# MCU.net
KiCad netlist of a schematic drawn in Altium Designer
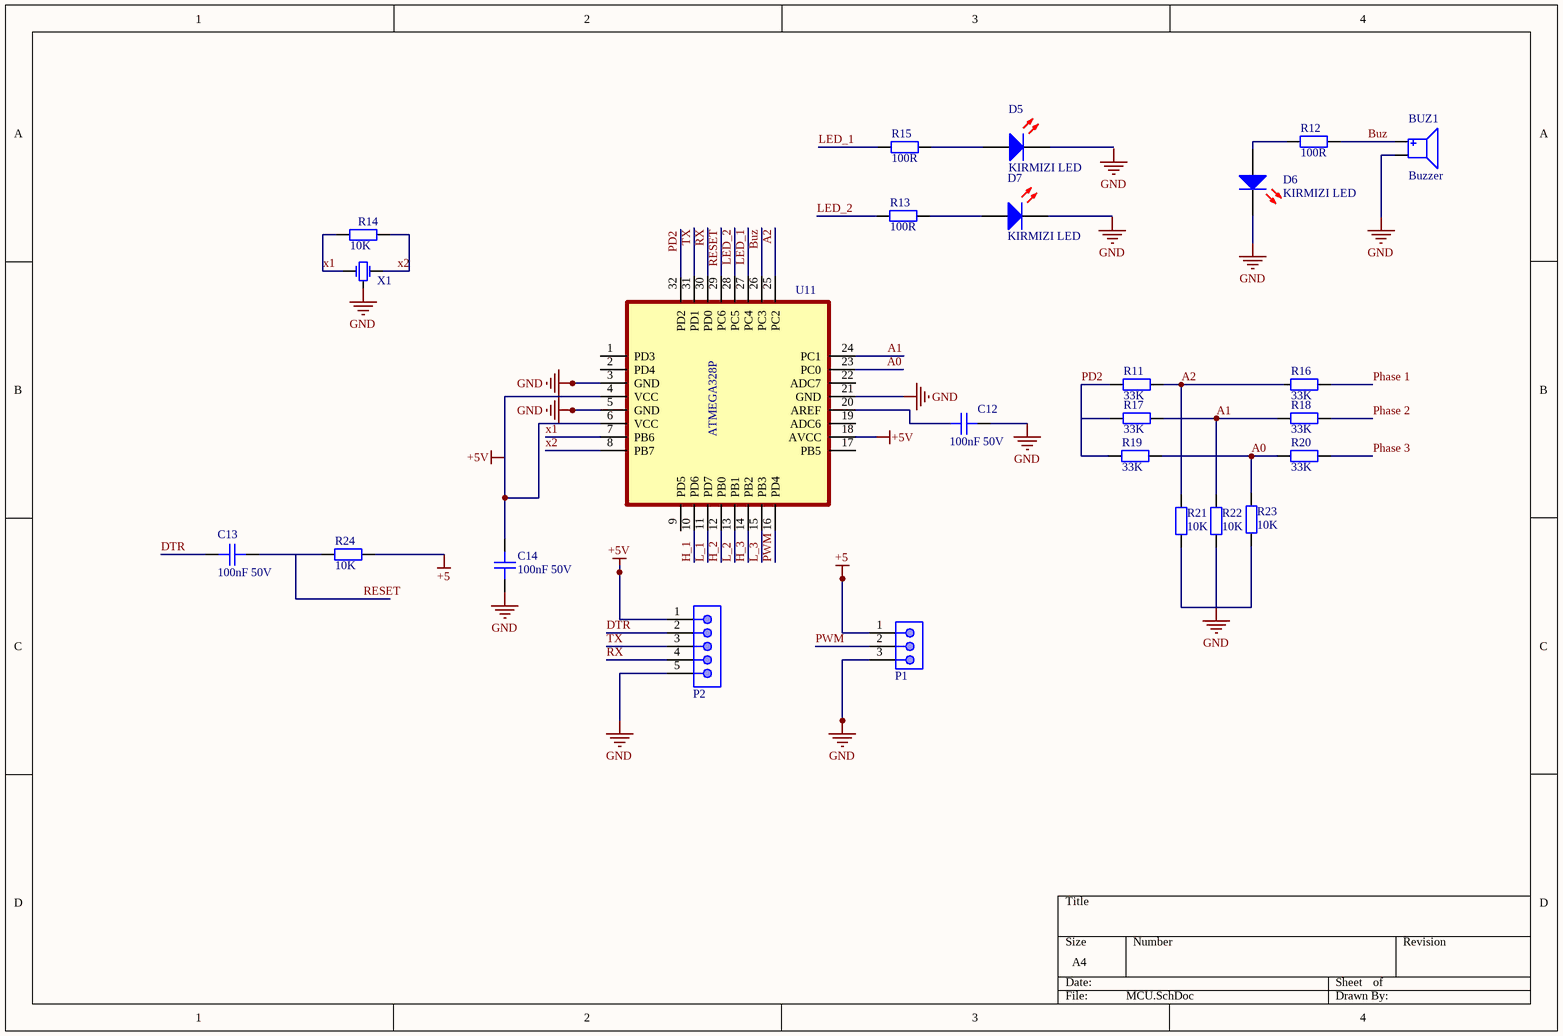
[diagram p0: MCU.SchDoc]

(export (version "E")
  (design (tool "Eeschema 10.0.6"))
  (components
    (comp (ref "BUZ1")
      (value "BUZZER MAGN 3.6V 7.5X7.5MM SMD")
      (footprint "BUZ: CMT-7525")
      (fields (field (name "DEGER") "Buzzer"))
      (libsource (lib "PROJE") (part "Buzzer(CMT-7525-80-SMT-TR)"))
    )
    (comp (ref "C12")
      (value "CAP CER 0.1UF 50V X7R 0805")
      (footprint "CAP 0805/2012")
      (description "0.1µF ±10% 50V Ceramic Capacitor X7R 0805 (2012 Metric)")
      (fields (field (name "DEGER") "100nF 50V"))
      (libsource (lib "PROJE") (part "100nF 50V 0805"))
    )
    (comp (ref "C13")
      (value "CAP CER 0.1UF 50V X7R 0805")
      (footprint "CAP 0805/2012")
      (description "0.1µF ±10% 50V Ceramic Capacitor X7R 0805 (2012 Metric)")
      (fields (field (name "DEGER") "100nF 50V"))
      (libsource (lib "PROJE") (part "100nF 50V 0805"))
    )
    (comp (ref "C14")
      (value "CAP CER 0.1UF 50V X7R 0805")
      (footprint "CAP 0805/2012")
      (description "0.1µF ±10% 50V Ceramic Capacitor X7R 0805 (2012 Metric)")
      (fields (field (name "DEGER") "100nF 50V"))
      (libsource (lib "PROJE") (part "100nF 50V 0805"))
    )
    (comp (ref "D5")
      (value "Red 645nm LED Indication - Discrete 1.8V 0805")
      (footprint "SMD: LED 0805/2012 RED")
      (description "LED RED DIFFUSED 0805 SMD")
      (fields (field (name "DEGER") "KIRMIZI LED"))
      (libsource (lib "PROJE") (part "LED_Kırmızı"))
    )
    (comp (ref "D6")
      (value "Red 645nm LED Indication - Discrete 1.8V 0805")
      (footprint "SMD: LED 0805/2012 RED")
      (description "LED RED DIFFUSED 0805 SMD")
      (fields (field (name "DEGER") "KIRMIZI LED"))
      (libsource (lib "PROJE") (part "LED_Kırmızı"))
    )
    (comp (ref "D7")
      (value "Red 645nm LED Indication - Discrete 1.8V 0805")
      (footprint "SMD: LED 0805/2012 RED")
      (description "LED RED DIFFUSED 0805 SMD")
      (fields (field (name "DEGER") "KIRMIZI LED"))
      (libsource (lib "PROJE") (part "LED_Kırmızı"))
    )
    (comp (ref "P1")
      (value "WR-PHD 2.54 mm Angled Socket Header")
      (footprint "PWM_CONN")
      (libsource (lib "PROJE") (part "HDR(1X3)"))
    )
    (comp (ref "P2")
      (value "WR-PHD 2.54 mm Angled Socket Header")
      (footprint "TTL_CONN_5")
      (libsource (lib "PROJE") (part "HDR(1X5)"))
    )
    (comp (ref "R11")
      (value "RES SMD 33K OHM 1% 1/8W 0805")
      (footprint "RES_0805")
      (description "33 kOhms ±1% 0.125W, 1/8W Chip Resistor 0805 (2012 Metric) Moisture Resistant Thick Film")
      (fields (field (name "DEGER") "33K"))
      (libsource (lib "PROJE") (part "33K 0805"))
    )
    (comp (ref "R12")
      (value "RES SMD 100 OHM 1% 1/8W 0805")
      (footprint "RES_0805")
      (description "100 Ohms ±1% 0.125W, 1/8W Chip Resistor 0805 (2012 Metric) Moisture Resistant Thick Film")
      (fields (field (name "DEGER") "100R"))
      (libsource (lib "PROJE") (part "100R 0805"))
    )
    (comp (ref "R13")
      (value "RES SMD 100 OHM 1% 1/8W 0805")
      (footprint "RES_0805")
      (description "100 Ohms ±1% 0.125W, 1/8W Chip Resistor 0805 (2012 Metric) Moisture Resistant Thick Film")
      (fields (field (name "DEGER") "100R"))
      (libsource (lib "PROJE") (part "100R 0805"))
    )
    (comp (ref "R14")
      (value "RES SMD 10K OHM 1% 1/8W 0805")
      (footprint "RES_0805")
      (description "10 kOhms ±1% 0.125W, 1/8W Chip Resistor 0805 (2012 Metric) Moisture Resistant Thick Film")
      (fields (field (name "DEGER") "10K"))
      (libsource (lib "") (part "10K 0805_1"))
    )
    (comp (ref "R15")
      (value "RES SMD 100 OHM 1% 1/8W 0805")
      (footprint "RES_0805")
      (description "100 Ohms ±1% 0.125W, 1/8W Chip Resistor 0805 (2012 Metric) Moisture Resistant Thick Film")
      (fields (field (name "DEGER") "100R"))
      (libsource (lib "PROJE") (part "100R 0805"))
    )
    (comp (ref "R16")
      (value "RES SMD 33K OHM 1% 1/8W 0805")
      (footprint "RES_0805")
      (description "33 kOhms ±1% 0.125W, 1/8W Chip Resistor 0805 (2012 Metric) Moisture Resistant Thick Film")
      (fields (field (name "DEGER") "33K"))
      (libsource (lib "PROJE") (part "33K 0805"))
    )
    (comp (ref "R17")
      (value "RES SMD 33K OHM 1% 1/8W 0805")
      (footprint "RES_0805")
      (description "33 kOhms ±1% 0.125W, 1/8W Chip Resistor 0805 (2012 Metric) Moisture Resistant Thick Film")
      (fields (field (name "DEGER") "33K"))
      (libsource (lib "PROJE") (part "33K 0805"))
    )
    (comp (ref "R18")
      (value "RES SMD 33K OHM 1% 1/8W 0805")
      (footprint "RES_0805")
      (description "33 kOhms ±1% 0.125W, 1/8W Chip Resistor 0805 (2012 Metric) Moisture Resistant Thick Film")
      (fields (field (name "DEGER") "33K"))
      (libsource (lib "PROJE") (part "33K 0805"))
    )
    (comp (ref "R19")
      (value "RES SMD 33K OHM 1% 1/8W 0805")
      (footprint "RES_0805")
      (description "33 kOhms ±1% 0.125W, 1/8W Chip Resistor 0805 (2012 Metric) Moisture Resistant Thick Film")
      (fields (field (name "DEGER") "33K"))
      (libsource (lib "PROJE") (part "33K 0805"))
    )
    (comp (ref "R20")
      (value "RES SMD 33K OHM 1% 1/8W 0805")
      (footprint "RES_0805")
      (description "33 kOhms ±1% 0.125W, 1/8W Chip Resistor 0805 (2012 Metric) Moisture Resistant Thick Film")
      (fields (field (name "DEGER") "33K"))
      (libsource (lib "PROJE") (part "33K 0805"))
    )
    (comp (ref "R21")
      (value "RES SMD 10K OHM 1% 1/8W 0805")
      (footprint "RES_0805")
      (description "10 kOhms ±1% 0.125W, 1/8W Chip Resistor 0805 (2012 Metric) Moisture Resistant Thick Film")
      (fields (field (name "DEGER") "10K"))
      (libsource (lib "PROJE") (part "10K 0805"))
    )
    (comp (ref "R22")
      (value "RES SMD 10K OHM 1% 1/8W 0805")
      (footprint "RES_0805")
      (description "10 kOhms ±1% 0.125W, 1/8W Chip Resistor 0805 (2012 Metric) Moisture Resistant Thick Film")
      (fields (field (name "DEGER") "10K"))
      (libsource (lib "PROJE") (part "10K 0805"))
    )
    (comp (ref "R23")
      (value "RES SMD 10K OHM 1% 1/8W 0805")
      (footprint "RES_0805")
      (description "10 kOhms ±1% 0.125W, 1/8W Chip Resistor 0805 (2012 Metric) Moisture Resistant Thick Film")
      (fields (field (name "DEGER") "10K"))
      (libsource (lib "PROJE") (part "10K 0805"))
    )
    (comp (ref "R24")
      (value "RES SMD 10K OHM 1% 1/8W 0805")
      (footprint "RES_0805")
      (description "10 kOhms ±1% 0.125W, 1/8W Chip Resistor 0805 (2012 Metric) Moisture Resistant Thick Film")
      (fields (field (name "DEGER") "10K"))
      (libsource (lib "") (part "10K 0805_1"))
    )
    (comp (ref "U11")
      (value "IC MCU 8BIT 32KB FLASH 32TQFP")
      (footprint "TQFP32")
      (description "AVR AVR® ATmega Microcontroller IC 8-Bit 20MHz 32KB (16K x 16) FLASH 32-TQFP (7x7)")
      (fields (field (name "DEGER") "ATMEGA328P"))
      (libsource (lib "PROJE") (part "ATMEGA328P"))
    )
    (comp (ref "X1")
      (value "CERAMIC RES 16.0000MHZ 15PF SMD")
      (footprint "CRYSTAL_16MHZ(CTSE16)")
      (description "16MHz Ceramic Resonator Built in Capacitor 15pF ±0.3%  -20°C ~ 80°C Surface Mount")
      (libsource (lib "PROJE") (part "CRYSTAL 16.0000MHZ(CSTCE16M0V53-R0)"))
    )
  )
  (nets
    (net (code "1") (name "+5") (class "Default")
      (node (ref "P1") (pin "1") (pinfunction "1_1") (pintype "passive"))
      (node (ref "R24") (pin "2") (pinfunction "2_2") (pintype "passive"))
    )
    (net (code "2") (name "+5V") (class "Default")
      (node (ref "C14") (pin "1") (pinfunction "1_1") (pintype "passive"))
      (node (ref "P2") (pin "1") (pinfunction "1_1") (pintype "passive"))
      (node (ref "U11") (pin "18") (pinfunction "AVCC_18") (pintype "passive"))
      (node (ref "U11") (pin "4") (pinfunction "VCC_4") (pintype "passive"))
      (node (ref "U11") (pin "6") (pinfunction "VCC_6") (pintype "passive"))
    )
    (net (code "3") (name "/A0") (class "Default")
      (node (ref "R19") (pin "2") (pinfunction "2_2") (pintype "passive"))
      (node (ref "R20") (pin "1") (pinfunction "1_1") (pintype "passive"))
      (node (ref "R23") (pin "2") (pinfunction "2_2") (pintype "passive"))
      (node (ref "U11") (pin "23") (pinfunction "PC0_23") (pintype "passive"))
    )
    (net (code "4") (name "/A1") (class "Default")
      (node (ref "R17") (pin "2") (pinfunction "2_2") (pintype "passive"))
      (node (ref "R18") (pin "1") (pinfunction "1_1") (pintype "passive"))
      (node (ref "R22") (pin "2") (pinfunction "2_2") (pintype "passive"))
      (node (ref "U11") (pin "24") (pinfunction "PC1_24") (pintype "passive"))
    )
    (net (code "5") (name "/A2") (class "Default")
      (node (ref "R11") (pin "2") (pinfunction "2_2") (pintype "passive"))
      (node (ref "R16") (pin "1") (pinfunction "1_1") (pintype "passive"))
      (node (ref "R21") (pin "2") (pinfunction "2_2") (pintype "passive"))
      (node (ref "U11") (pin "25") (pinfunction "PC2_25") (pintype "passive"))
    )
    (net (code "6") (name "/Buz") (class "Default")
      (node (ref "BUZ1") (pin "1") (pinfunction "Positive_1") (pintype "passive"))
      (node (ref "R12") (pin "2") (pinfunction "2_2") (pintype "passive"))
      (node (ref "U11") (pin "26") (pinfunction "PC3_26") (pintype "passive"))
    )
    (net (code "7") (name "/DTR") (class "Default")
      (node (ref "C13") (pin "1") (pinfunction "1_1") (pintype "passive"))
      (node (ref "P2") (pin "2") (pinfunction "2_2") (pintype "passive"))
    )
    (net (code "8") (name "/H_1") (class "Default")
      (node (ref "U11") (pin "10") (pinfunction "PD6_10") (pintype "passive"))
    )
    (net (code "9") (name "/H_2") (class "Default")
      (node (ref "U11") (pin "12") (pinfunction "PB0_12") (pintype "passive"))
    )
    (net (code "10") (name "/H_3") (class "Default")
      (node (ref "U11") (pin "14") (pinfunction "PB2_14") (pintype "passive"))
    )
    (net (code "11") (name "/LED_1") (class "Default")
      (node (ref "R15") (pin "1") (pinfunction "1_1") (pintype "passive"))
      (node (ref "U11") (pin "27") (pinfunction "PC4_27") (pintype "passive"))
    )
    (net (code "12") (name "/LED_2") (class "Default")
      (node (ref "R13") (pin "1") (pinfunction "1_1") (pintype "passive"))
      (node (ref "U11") (pin "28") (pinfunction "PC5_28") (pintype "passive"))
    )
    (net (code "13") (name "/L_1") (class "Default")
      (node (ref "U11") (pin "11") (pinfunction "PD7_11") (pintype "passive"))
    )
    (net (code "14") (name "/L_2") (class "Default")
      (node (ref "U11") (pin "13") (pinfunction "PB1_13") (pintype "passive"))
    )
    (net (code "15") (name "/L_3") (class "Default")
      (node (ref "U11") (pin "15") (pinfunction "PB3_15") (pintype "passive"))
    )
    (net (code "16") (name "/PD2") (class "Default")
      (node (ref "R11") (pin "1") (pinfunction "1_1") (pintype "passive"))
      (node (ref "R17") (pin "1") (pinfunction "1_1") (pintype "passive"))
      (node (ref "R19") (pin "1") (pinfunction "1_1") (pintype "passive"))
      (node (ref "U11") (pin "32") (pinfunction "PD2_32") (pintype "passive"))
    )
    (net (code "17") (name "/PWM") (class "Default")
      (node (ref "P1") (pin "2") (pinfunction "2_2") (pintype "passive"))
      (node (ref "U11") (pin "16") (pinfunction "PD4_16") (pintype "passive"))
    )
    (net (code "18") (name "/Phase 1") (class "Default")
      (node (ref "R16") (pin "2") (pinfunction "2_2") (pintype "passive"))
    )
    (net (code "19") (name "/Phase 2") (class "Default")
      (node (ref "R18") (pin "2") (pinfunction "2_2") (pintype "passive"))
    )
    (net (code "20") (name "/Phase 3") (class "Default")
      (node (ref "R20") (pin "2") (pinfunction "2_2") (pintype "passive"))
    )
    (net (code "21") (name "/RESET") (class "Default")
      (node (ref "C13") (pin "2") (pinfunction "2_2") (pintype "passive"))
      (node (ref "R24") (pin "1") (pinfunction "1_1") (pintype "passive"))
      (node (ref "U11") (pin "29") (pinfunction "PC6_29") (pintype "passive"))
    )
    (net (code "22") (name "/RX") (class "Default")
      (node (ref "P2") (pin "4") (pinfunction "4_4") (pintype "passive"))
      (node (ref "U11") (pin "30") (pinfunction "PD0_30") (pintype "passive"))
    )
    (net (code "23") (name "/TX") (class "Default")
      (node (ref "P2") (pin "3") (pinfunction "3_3") (pintype "passive"))
      (node (ref "U11") (pin "31") (pinfunction "PD1_31") (pintype "passive"))
    )
    (net (code "24") (name "/x1") (class "Default")
      (node (ref "R14") (pin "1") (pinfunction "1_1") (pintype "passive"))
      (node (ref "U11") (pin "7") (pinfunction "PB6_7") (pintype "passive"))
      (node (ref "X1") (pin "1") (pinfunction "OSC1_1") (pintype "passive"))
    )
    (net (code "25") (name "/x2") (class "Default")
      (node (ref "R14") (pin "2") (pinfunction "2_2") (pintype "passive"))
      (node (ref "U11") (pin "8") (pinfunction "PB7_8") (pintype "passive"))
      (node (ref "X1") (pin "3") (pinfunction "OSC2_3") (pintype "passive"))
    )
    (net (code "26") (name "GND") (class "Default")
      (node (ref "BUZ1") (pin "2") (pinfunction "Negative_2") (pintype "passive"))
      (node (ref "C12") (pin "2") (pinfunction "2_2") (pintype "passive"))
      (node (ref "C14") (pin "2") (pinfunction "2_2") (pintype "passive"))
      (node (ref "D6") (pin "2") (pinfunction "K_2") (pintype "passive"))
      (node (ref "P1") (pin "3") (pinfunction "3_3") (pintype "passive"))
      (node (ref "P2") (pin "5") (pinfunction "5_5") (pintype "passive"))
      (node (ref "R21") (pin "1") (pinfunction "1_1") (pintype "passive"))
      (node (ref "R22") (pin "1") (pinfunction "1_1") (pintype "passive"))
      (node (ref "R23") (pin "1") (pinfunction "1_1") (pintype "passive"))
      (node (ref "U11") (pin "21") (pinfunction "GND_21") (pintype "passive"))
      (node (ref "U11") (pin "3") (pinfunction "GND_3") (pintype "passive"))
      (node (ref "U11") (pin "5") (pinfunction "GND_5") (pintype "passive"))
      (node (ref "X1") (pin "2") (pinfunction "GND_2") (pintype "passive"))
    )
    (net (code "27") (name "Net-(D5-A)") (class "Default")
      (node (ref "D5") (pin "1") (pinfunction "A_1") (pintype "passive"))
      (node (ref "R15") (pin "2") (pinfunction "2_2") (pintype "passive"))
    )
    (net (code "28") (name "Net-(D6-A)") (class "Default")
      (node (ref "D6") (pin "1") (pinfunction "A_1") (pintype "passive"))
      (node (ref "R12") (pin "1") (pinfunction "1_1") (pintype "passive"))
    )
    (net (code "29") (name "Net-(D7-A)") (class "Default")
      (node (ref "D7") (pin "1") (pinfunction "A_1") (pintype "passive"))
      (node (ref "R13") (pin "2") (pinfunction "2_2") (pintype "passive"))
    )
    (net (code "30") (name "Net-(U11-AREF)") (class "Default")
      (node (ref "C12") (pin "1") (pinfunction "1_1") (pintype "passive"))
      (node (ref "U11") (pin "20") (pinfunction "AREF_20") (pintype "passive"))
    )
    (net (code "31") (name "unconnected-(D5-K-Pad2)") (class "Default")
      (node (ref "D5") (pin "2") (pinfunction "K_2") (pintype "passive"))
    )
    (net (code "32") (name "unconnected-(D7-K-Pad2)") (class "Default")
      (node (ref "D7") (pin "2") (pinfunction "K_2") (pintype "passive"))
    )
    (net (code "33") (name "unconnected-(U11-ADC6-Pad19)") (class "Default")
      (node (ref "U11") (pin "19") (pinfunction "ADC6_19") (pintype "passive"))
    )
    (net (code "34") (name "unconnected-(U11-ADC7-Pad22)") (class "Default")
      (node (ref "U11") (pin "22") (pinfunction "ADC7_22") (pintype "passive"))
    )
    (net (code "35") (name "unconnected-(U11-PB5-Pad17)") (class "Default")
      (node (ref "U11") (pin "17") (pinfunction "PB5_17") (pintype "passive"))
    )
    (net (code "36") (name "unconnected-(U11-PD3-Pad1)") (class "Default")
      (node (ref "U11") (pin "1") (pinfunction "PD3_1") (pintype "passive"))
    )
    (net (code "37") (name "unconnected-(U11-PD4-Pad2)") (class "Default")
      (node (ref "U11") (pin "2") (pinfunction "PD4_2") (pintype "passive"))
    )
    (net (code "38") (name "unconnected-(U11-PD5-Pad9)") (class "Default")
      (node (ref "U11") (pin "9") (pinfunction "PD5_9") (pintype "passive"))
    )
  )
)
